# KMO_IO_MV8.net
KiCad netlist of a schematic drawn in EAGLE
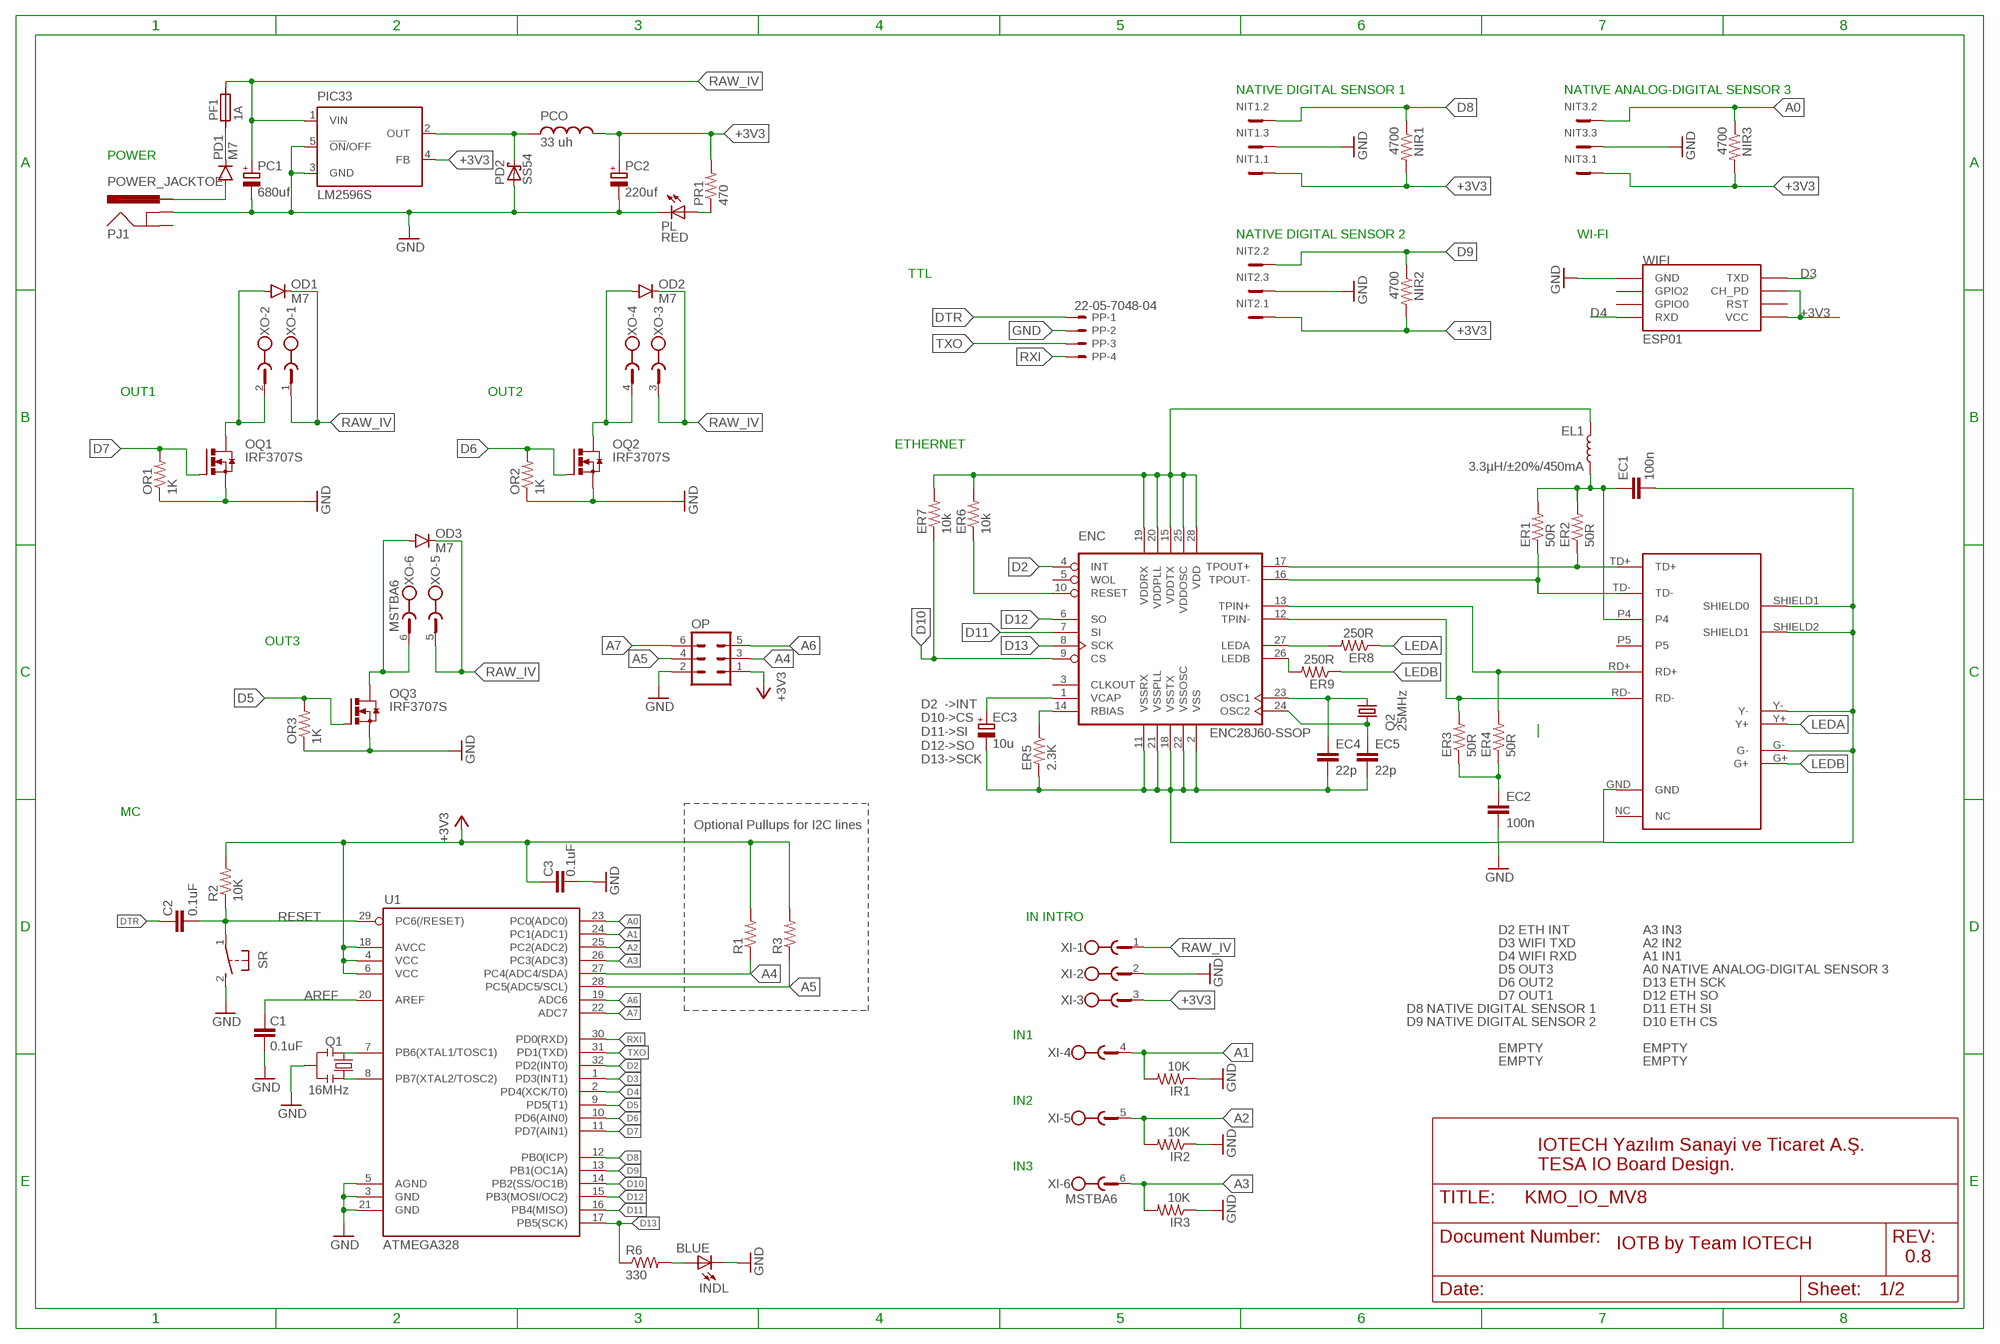
[diagram p0: schematic, sheet 1]
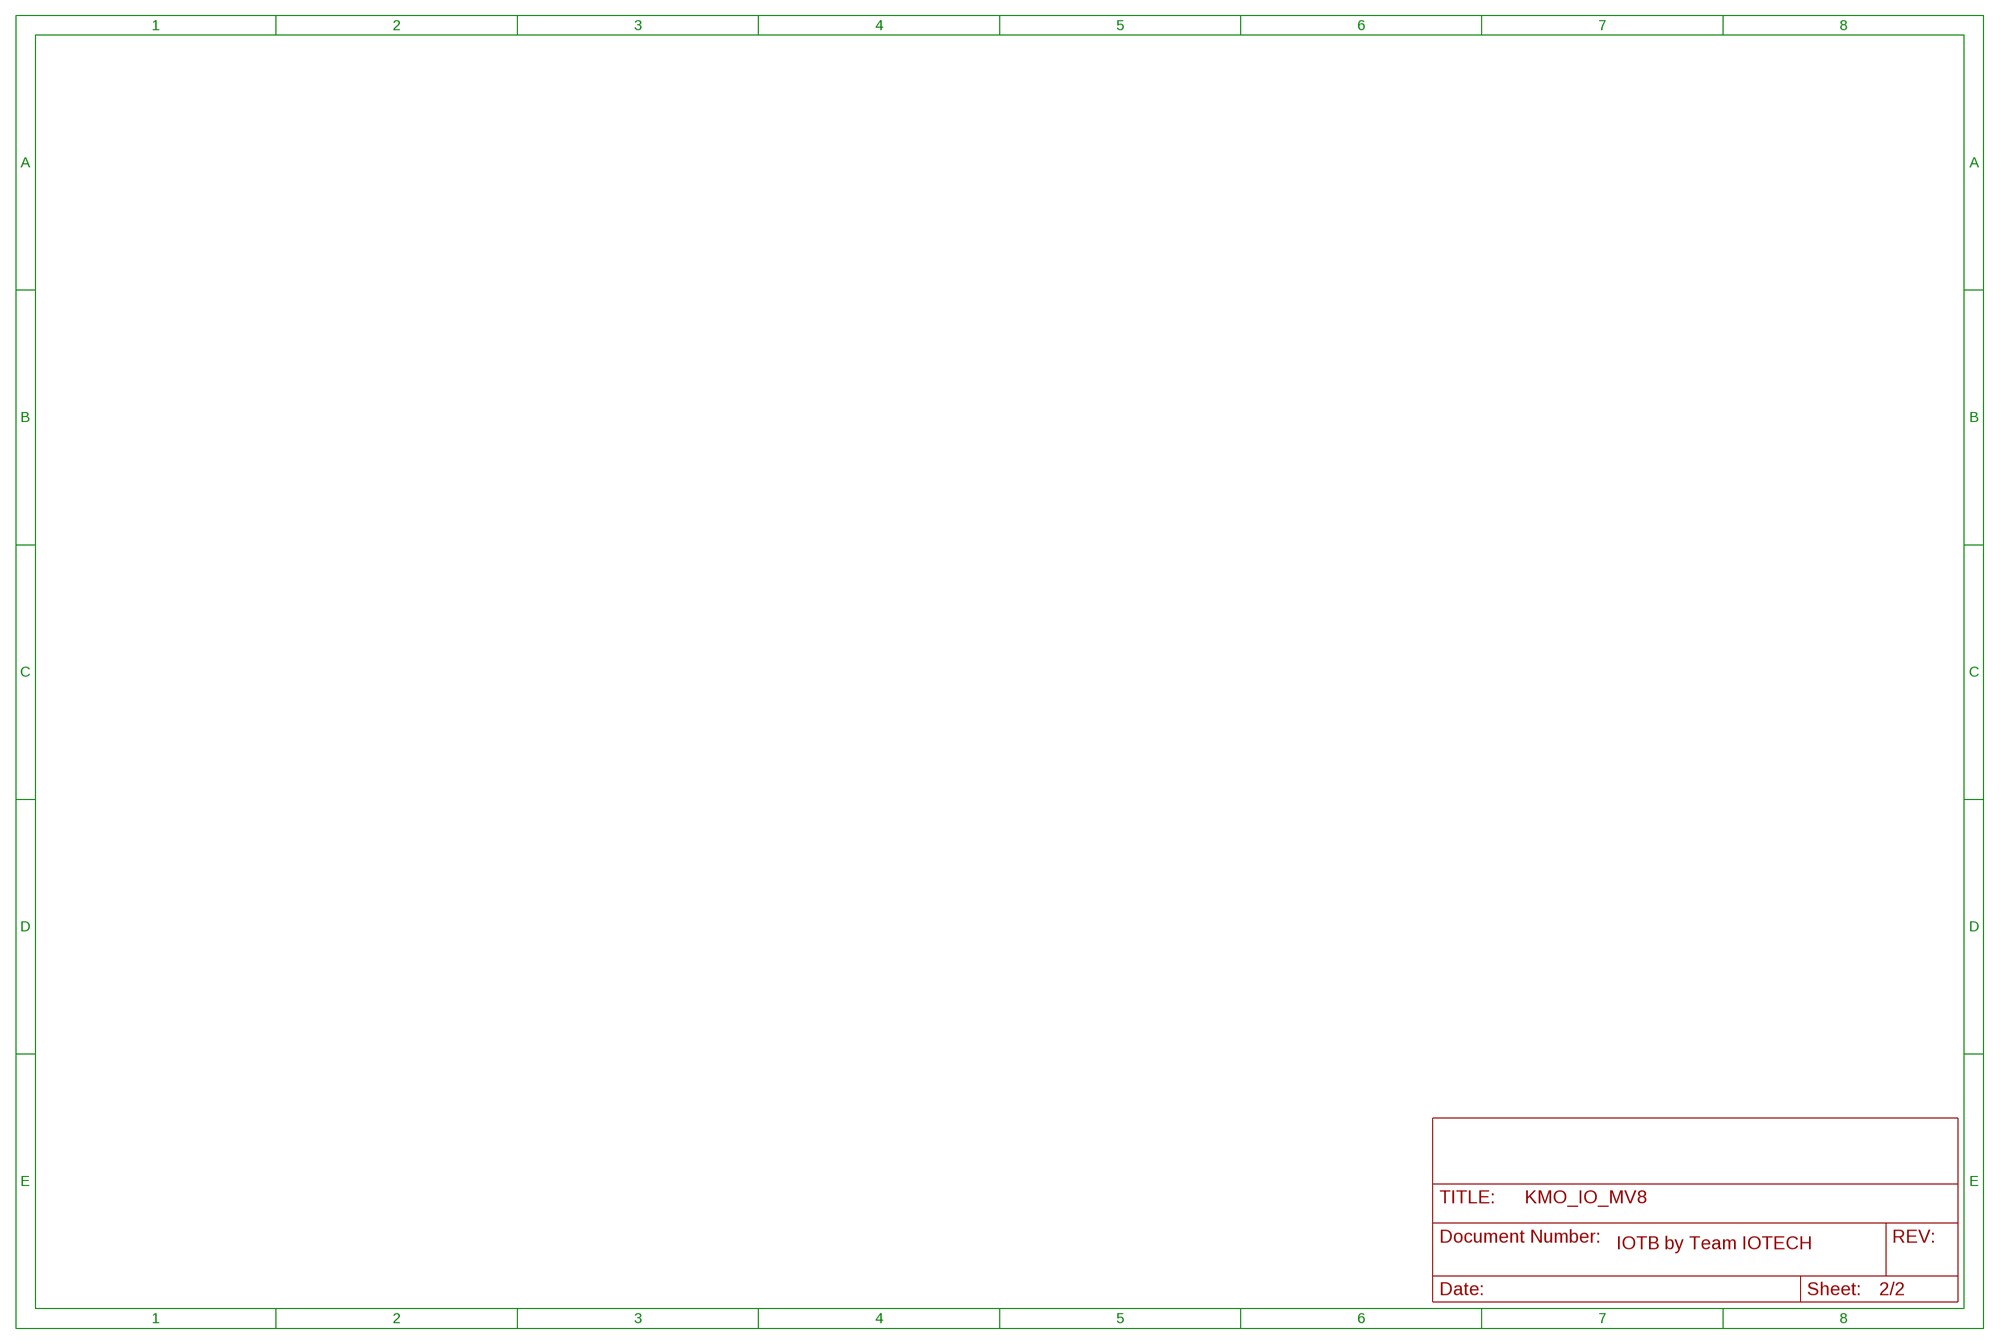
[diagram p1: schematic, sheet 2]

(export (version "E")
  (design (tool "Eeschema 10.0.6"))
  (components
    (comp (ref "C1")
      (value "0.1uF")
      (footprint "eagle-import:0805")
      (libsource (lib "eagle-import") (part "CAP0805"))
    )
    (comp (ref "C2")
      (value "0.1uF")
      (footprint "eagle-import:0805")
      (libsource (lib "eagle-import") (part "CAP0805"))
    )
    (comp (ref "C3")
      (value "0.1uF")
      (footprint "eagle-import:0805")
      (libsource (lib "eagle-import") (part "CAP0805"))
    )
    (comp (ref "EC1")
      (value "100n")
      (footprint "eagle-import:0805")
      (libsource (lib "eagle-import") (part "CAP0805"))
    )
    (comp (ref "EC2")
      (value "100n")
      (footprint "eagle-import:0805")
      (libsource (lib "eagle-import") (part "CAP0805"))
    )
    (comp (ref "EC3")
      (value "10u")
      (footprint "eagle-import:CT3216")
      (libsource (lib "eagle-import") (part "CPOL-EUCT3216"))
    )
    (comp (ref "EC4")
      (value "22p")
      (footprint "eagle-import:0805")
      (libsource (lib "eagle-import") (part "CAP0805"))
    )
    (comp (ref "EC5")
      (value "22p")
      (footprint "eagle-import:0805")
      (libsource (lib "eagle-import") (part "CAP0805"))
    )
    (comp (ref "EL1")
      (value "3.3µH/±20%/450mA")
      (footprint "eagle-import:0805")
      (libsource (lib "eagle-import") (part "INDUCTOR-0805-3.3UH"))
    )
    (comp (ref "ENC")
      (value "ENC28J60-SSOP")
      (footprint "eagle-import:SSOP28")
      (libsource (lib "eagle-import") (part "ENC28J60-SSOP"))
    )
    (comp (ref "ER1")
      (value "50R")
      (footprint "eagle-import:0805")
      (libsource (lib "eagle-import") (part "RESISTOR0805-RES"))
    )
    (comp (ref "ER2")
      (value "50R")
      (footprint "eagle-import:0805")
      (libsource (lib "eagle-import") (part "RESISTOR0805-RES"))
    )
    (comp (ref "ER3")
      (value "50R")
      (footprint "eagle-import:0805")
      (libsource (lib "eagle-import") (part "RESISTOR0805-RES"))
    )
    (comp (ref "ER4")
      (value "50R")
      (footprint "eagle-import:0805")
      (libsource (lib "eagle-import") (part "RESISTOR0805-RES"))
    )
    (comp (ref "ER5")
      (value "2.3K")
      (footprint "eagle-import:0805")
      (libsource (lib "eagle-import") (part "RESISTOR0805-RES"))
    )
    (comp (ref "ER6")
      (value "10k")
      (footprint "eagle-import:0805")
      (libsource (lib "eagle-import") (part "RESISTOR0805-RES"))
    )
    (comp (ref "ER7")
      (value "10k")
      (footprint "eagle-import:0805")
      (libsource (lib "eagle-import") (part "RESISTOR0805-RES"))
    )
    (comp (ref "ER8")
      (value "250R")
      (footprint "eagle-import:0805")
      (libsource (lib "eagle-import") (part "RESISTOR0805-RES"))
    )
    (comp (ref "ER9")
      (value "250R")
      (footprint "eagle-import:0805")
      (libsource (lib "eagle-import") (part "RESISTOR0805-RES"))
    )
    (comp (ref "INDL")
      (value "BLUE")
      (footprint "eagle-import:CHIP-LED0805")
      (libsource (lib "eagle-import") (part "LEDCHIP-LED0805"))
    )
    (comp (ref "IR1")
      (value "10K")
      (footprint "eagle-import:0805")
      (libsource (lib "eagle-import") (part "RESISTOR0805-RES"))
    )
    (comp (ref "IR2")
      (value "10K")
      (footprint "eagle-import:0805")
      (libsource (lib "eagle-import") (part "RESISTOR0805-RES"))
    )
    (comp (ref "IR3")
      (value "10K")
      (footprint "eagle-import:0805")
      (libsource (lib "eagle-import") (part "RESISTOR0805-RES"))
    )
    (comp (ref "NIR1")
      (value "4700")
      (footprint "eagle-import:0805")
      (libsource (lib "eagle-import") (part "RESISTOR0805-RES"))
    )
    (comp (ref "NIR2")
      (value "4700")
      (footprint "eagle-import:0805")
      (libsource (lib "eagle-import") (part "RESISTOR0805-RES"))
    )
    (comp (ref "NIR3")
      (value "4700")
      (footprint "eagle-import:0805")
      (libsource (lib "eagle-import") (part "RESISTOR0805-RES"))
    )
    (comp (ref "NIT1")
      (value "MC3")
      (footprint "eagle-import:MC3")
      (libsource (lib "eagle-import") (part "MC3"))
    )
    (comp (ref "NIT2")
      (value "MC3")
      (footprint "eagle-import:MC3")
      (libsource (lib "eagle-import") (part "MC3"))
    )
    (comp (ref "NIT3")
      (value "MC3")
      (footprint "eagle-import:MC3")
      (libsource (lib "eagle-import") (part "MC3"))
    )
    (comp (ref "OD1")
      (value "M7")
      (footprint "eagle-import:SMA-DIODE")
      (libsource (lib "eagle-import") (part "DIODESMA"))
    )
    (comp (ref "OD2")
      (value "M7")
      (footprint "eagle-import:SMA-DIODE")
      (libsource (lib "eagle-import") (part "DIODESMA"))
    )
    (comp (ref "OD3")
      (value "M7")
      (footprint "eagle-import:SMA-DIODE")
      (libsource (lib "eagle-import") (part "DIODESMA"))
    )
    (comp (ref "OP")
      (value "MA03-2")
      (footprint "eagle-import:MA03-2")
      (libsource (lib "eagle-import") (part "MA03-2"))
    )
    (comp (ref "OQ1")
      (value "IRF3707S")
      (footprint "eagle-import:D2PACK")
      (libsource (lib "eagle-import") (part "IRF3704S"))
    )
    (comp (ref "OQ2")
      (value "IRF3707S")
      (footprint "eagle-import:D2PACK")
      (libsource (lib "eagle-import") (part "IRF3704S"))
    )
    (comp (ref "OQ3")
      (value "IRF3707S")
      (footprint "eagle-import:D2PACK")
      (libsource (lib "eagle-import") (part "IRF3704S"))
    )
    (comp (ref "OR1")
      (value "1K")
      (footprint "eagle-import:0805")
      (libsource (lib "eagle-import") (part "RESISTOR0805-RES"))
    )
    (comp (ref "OR2")
      (value "1K")
      (footprint "eagle-import:0805")
      (libsource (lib "eagle-import") (part "RESISTOR0805-RES"))
    )
    (comp (ref "OR3")
      (value "1K")
      (footprint "eagle-import:0805")
      (libsource (lib "eagle-import") (part "RESISTOR0805-RES"))
    )
    (comp (ref "PC1")
      (value "680uf")
      (footprint "eagle-import:140CLH-1010")
      (libsource (lib "eagle-import") (part "CPOL-EU140CLH-1010"))
    )
    (comp (ref "PC2")
      (value "220uf")
      (footprint "eagle-import:140CLH-1010")
      (libsource (lib "eagle-import") (part "CPOL-EU140CLH-1010"))
    )
    (comp (ref "PCO")
      (value "33 uh")
      (footprint "eagle-import:MSS1260")
      (libsource (lib "eagle-import") (part "MSS1260"))
    )
    (comp (ref "PD1")
      (value "M7")
      (footprint "eagle-import:SMA-DIODE")
      (libsource (lib "eagle-import") (part "DIODESMA"))
    )
    (comp (ref "PD2")
      (value "SS54")
      (footprint "eagle-import:SMB")
      (libsource (lib "eagle-import") (part "SCHOTTKY-DIODESMD"))
    )
    (comp (ref "PF1")
      (value "1A")
      (footprint "eagle-import:1820")
      (libsource (lib "eagle-import") (part "SIBA194600"))
    )
    (comp (ref "PIC33")
      (value "LM2596S")
      (footprint "eagle-import:TO263-5")
      (fields (field (name "MF") "NATIONAL SEMICONDUCTOR") (field (name "MPN") "LM2596S-ADJ/NOPB"))
      (libsource (lib "eagle-import") (part "LM2596S"))
    )
    (comp (ref "PJ1")
      (value "POWER_JACKTOE")
      (footprint "eagle-import:POWER_JACK_SMD_OVERPASTE_TOE")
      (libsource (lib "eagle-import") (part "POWER_JACKTOE"))
    )
    (comp (ref "PL")
      (value "RED")
      (footprint "eagle-import:CHIP-LED0805")
      (libsource (lib "eagle-import") (part "LEDCHIP-LED0805"))
    )
    (comp (ref "PP")
      (value "22-05-7048-04")
      (footprint "eagle-import:7395-04")
      (fields (field (name "MF") "MOLEX"))
      (libsource (lib "eagle-import") (part "22-?-0405-7048"))
    )
    (comp (ref "PR1")
      (value "470")
      (footprint "eagle-import:0805")
      (libsource (lib "eagle-import") (part "RESISTOR0805-RES"))
    )
    (comp (ref "Q1")
      (value "16MHz")
      (footprint "eagle-import:RESONATOR-SMD-1_1")
      (libsource (lib "eagle-import") (part "RESONATOR1{colon}1"))
    )
    (comp (ref "Q2")
      (value "25MHz")
      (footprint "eagle-import:5.0X3.2_2")
      (libsource (lib "eagle-import") (part "KX-9B"))
    )
    (comp (ref "R1")
      (value "RESISTOR0805-RES")
      (footprint "eagle-import:0805")
      (libsource (lib "eagle-import") (part "RESISTOR0805-RES"))
    )
    (comp (ref "R2")
      (value "10K")
      (footprint "eagle-import:0805")
      (libsource (lib "eagle-import") (part "RESISTOR0805-RES"))
    )
    (comp (ref "R3")
      (value "RESISTOR0805-RES")
      (footprint "eagle-import:0805")
      (libsource (lib "eagle-import") (part "RESISTOR0805-RES"))
    )
    (comp (ref "R6")
      (value "330")
      (footprint "eagle-import:0805")
      (libsource (lib "eagle-import") (part "RESISTOR0805-RES"))
    )
    (comp (ref "SR")
      (value "31-XX")
      (footprint "eagle-import:B3F-31XX")
      (fields (field (name "MPN") "B3F-3100"))
      (libsource (lib "eagle-import") (part "31-XX"))
    )
    (comp (ref "U$2")
      (value "HR911105A")
      (footprint "eagle-import:RJ45")
      (libsource (lib "eagle-import") (part "HR911105A"))
    )
    (comp (ref "U1")
      (value "ATMEGA328")
      (footprint "eagle-import:TQFP32-08")
      (libsource (lib "eagle-import") (part "ATMEGA168"))
    )
    (comp (ref "WIFI")
      (value "ESP01")
      (footprint "eagle-import:ESP01")
      (libsource (lib "eagle-import") (part "ESP01"))
    )
    (comp (ref "XI")
      (value "MSTBA6")
      (footprint "eagle-import:MSTBA6")
      (fields (field (name "MF") "FARNELL") (field (name "MPN") "1757284"))
      (libsource (lib "eagle-import") (part "MSTBA6"))
    )
    (comp (ref "XO")
      (value "MSTBA6")
      (footprint "eagle-import:MSTBA6")
      (fields (field (name "MF") "FARNELL") (field (name "MPN") "1757284"))
      (libsource (lib "eagle-import") (part "MSTBA6"))
    )
  )
  (nets
    (net (code "1") (name "+3V3") (class "Default")
      (node (ref "C3") (pin "2") (pinfunction "2_2") (pintype "passive"))
      (node (ref "EL1") (pin "1") (pinfunction "1_1") (pintype "passive"))
      (node (ref "ENC") (pin "15") (pinfunction "VDDTX_15") (pintype "power_in"))
      (node (ref "ENC") (pin "19") (pinfunction "VDDRX_19") (pintype "power_in"))
      (node (ref "ENC") (pin "20") (pinfunction "VDDPLL_20") (pintype "power_in"))
      (node (ref "ENC") (pin "25") (pinfunction "VDDOSC_25") (pintype "power_in"))
      (node (ref "ENC") (pin "28") (pinfunction "VDD_28") (pintype "power_in"))
      (node (ref "ER6") (pin "2") (pinfunction "2_2") (pintype "passive"))
      (node (ref "ER7") (pin "2") (pinfunction "2_2") (pintype "passive"))
      (node (ref "NIR1") (pin "2") (pinfunction "2_2") (pintype "passive"))
      (node (ref "NIR2") (pin "2") (pinfunction "2_2") (pintype "passive"))
      (node (ref "NIR3") (pin "2") (pinfunction "2_2") (pintype "passive"))
      (node (ref "NIT1") (pin "1") (pinfunction "SK_1") (pintype "passive"))
      (node (ref "NIT2") (pin "1") (pinfunction "SK_1") (pintype "passive"))
      (node (ref "NIT3") (pin "1") (pinfunction "SK_1") (pintype "passive"))
      (node (ref "OP") (pin "1") (pinfunction "1_1") (pintype "passive"))
      (node (ref "PC2") (pin "+") (pinfunction "+_+") (pintype "passive"))
      (node (ref "PCO") (pin "P$1") (pinfunction "P$1_P$1") (pintype "passive"))
      (node (ref "PIC33") (pin "4") (pinfunction "FB_4") (pintype "input"))
      (node (ref "PR1") (pin "2") (pinfunction "2_2") (pintype "passive"))
      (node (ref "R1") (pin "2") (pinfunction "2_2") (pintype "passive"))
      (node (ref "R2") (pin "2") (pinfunction "2_2") (pintype "passive"))
      (node (ref "R3") (pin "2") (pinfunction "2_2") (pintype "passive"))
      (node (ref "U1") (pin "18") (pinfunction "AVCC_18") (pintype "bidirectional"))
      (node (ref "U1") (pin "4") (pinfunction "VCC_4") (pintype "bidirectional"))
      (node (ref "U1") (pin "6") (pinfunction "VCC_6") (pintype "bidirectional"))
      (node (ref "WIFI") (pin "CH_PD") (pinfunction "CH_PD_CH_PD") (pintype "bidirectional"))
      (node (ref "WIFI") (pin "VCC") (pinfunction "VCC_VCC") (pintype "bidirectional"))
      (node (ref "XI") (pin "3") (pinfunction "1_3") (pintype "passive"))
    )
    (net (code "2") (name "A0") (class "Default")
      (node (ref "NIR3") (pin "1") (pinfunction "1_1") (pintype "passive"))
      (node (ref "NIT3") (pin "2") (pinfunction "SK_2") (pintype "passive"))
      (node (ref "U1") (pin "23") (pinfunction "PC0(ADC0)_23") (pintype "bidirectional"))
    )
    (net (code "3") (name "A1") (class "Default")
      (node (ref "IR1") (pin "2") (pinfunction "2_2") (pintype "passive"))
      (node (ref "U1") (pin "24") (pinfunction "PC1(ADC1)_24") (pintype "bidirectional"))
      (node (ref "XI") (pin "4") (pinfunction "1_4") (pintype "passive"))
    )
    (net (code "4") (name "A2") (class "Default")
      (node (ref "IR2") (pin "2") (pinfunction "2_2") (pintype "passive"))
      (node (ref "U1") (pin "25") (pinfunction "PC2(ADC2)_25") (pintype "bidirectional"))
      (node (ref "XI") (pin "5") (pinfunction "1_5") (pintype "passive"))
    )
    (net (code "5") (name "A3") (class "Default")
      (node (ref "IR3") (pin "2") (pinfunction "2_2") (pintype "passive"))
      (node (ref "U1") (pin "26") (pinfunction "PC3(ADC3)_26") (pintype "bidirectional"))
      (node (ref "XI") (pin "6") (pinfunction "1_6") (pintype "passive"))
    )
    (net (code "6") (name "A4") (class "Default")
      (node (ref "OP") (pin "3") (pinfunction "3_3") (pintype "passive"))
      (node (ref "R1") (pin "1") (pinfunction "1_1") (pintype "passive"))
      (node (ref "U1") (pin "27") (pinfunction "PC4(ADC4/SDA)_27") (pintype "bidirectional"))
    )
    (net (code "7") (name "A5") (class "Default")
      (node (ref "OP") (pin "4") (pinfunction "4_4") (pintype "passive"))
      (node (ref "R3") (pin "1") (pinfunction "1_1") (pintype "passive"))
      (node (ref "U1") (pin "28") (pinfunction "PC5(ADC5/SCL)_28") (pintype "bidirectional"))
    )
    (net (code "8") (name "A6") (class "Default")
      (node (ref "OP") (pin "5") (pinfunction "5_5") (pintype "passive"))
      (node (ref "U1") (pin "19") (pinfunction "ADC6_19") (pintype "bidirectional"))
    )
    (net (code "9") (name "A7") (class "Default")
      (node (ref "OP") (pin "6") (pinfunction "6_6") (pintype "passive"))
      (node (ref "U1") (pin "22") (pinfunction "ADC7_22") (pintype "bidirectional"))
    )
    (net (code "10") (name "AREF") (class "Default")
      (node (ref "C1") (pin "2") (pinfunction "2_2") (pintype "passive"))
      (node (ref "U1") (pin "20") (pinfunction "AREF_20") (pintype "bidirectional"))
    )
    (net (code "11") (name "D2") (class "Default")
      (node (ref "ENC") (pin "4") (pinfunction "INT_4") (pintype "output"))
      (node (ref "U1") (pin "32") (pinfunction "PD2(INT0)_32") (pintype "bidirectional"))
    )
    (net (code "12") (name "D3") (class "Default")
      (node (ref "U1") (pin "1") (pinfunction "PD3(INT1)_1") (pintype "bidirectional"))
      (node (ref "WIFI") (pin "TX") (pinfunction "TXD_TX") (pintype "bidirectional"))
    )
    (net (code "13") (name "D4") (class "Default")
      (node (ref "U1") (pin "2") (pinfunction "PD4(XCK/T0)_2") (pintype "bidirectional"))
      (node (ref "WIFI") (pin "RX") (pinfunction "RXD_RX") (pintype "bidirectional"))
    )
    (net (code "14") (name "D5") (class "Default")
      (node (ref "OQ3") (pin "1") (pinfunction "G_1") (pintype "passive"))
      (node (ref "OR3") (pin "2") (pinfunction "2_2") (pintype "passive"))
      (node (ref "U1") (pin "9") (pinfunction "PD5(T1)_9") (pintype "bidirectional"))
    )
    (net (code "15") (name "D6") (class "Default")
      (node (ref "OQ2") (pin "1") (pinfunction "G_1") (pintype "passive"))
      (node (ref "OR2") (pin "2") (pinfunction "2_2") (pintype "passive"))
      (node (ref "U1") (pin "10") (pinfunction "PD6(AIN0)_10") (pintype "bidirectional"))
    )
    (net (code "16") (name "D7") (class "Default")
      (node (ref "OQ1") (pin "1") (pinfunction "G_1") (pintype "passive"))
      (node (ref "OR1") (pin "2") (pinfunction "2_2") (pintype "passive"))
      (node (ref "U1") (pin "11") (pinfunction "PD7(AIN1)_11") (pintype "bidirectional"))
    )
    (net (code "17") (name "D8") (class "Default")
      (node (ref "NIR1") (pin "1") (pinfunction "1_1") (pintype "passive"))
      (node (ref "NIT1") (pin "2") (pinfunction "SK_2") (pintype "passive"))
      (node (ref "U1") (pin "12") (pinfunction "PB0(ICP)_12") (pintype "bidirectional"))
    )
    (net (code "18") (name "D9") (class "Default")
      (node (ref "NIR2") (pin "1") (pinfunction "1_1") (pintype "passive"))
      (node (ref "NIT2") (pin "2") (pinfunction "SK_2") (pintype "passive"))
      (node (ref "U1") (pin "13") (pinfunction "PB1(OC1A)_13") (pintype "bidirectional"))
    )
    (net (code "19") (name "D10") (class "Default")
      (node (ref "ENC") (pin "9") (pinfunction "CS_9") (pintype "input"))
      (node (ref "ER7") (pin "1") (pinfunction "1_1") (pintype "passive"))
      (node (ref "U1") (pin "14") (pinfunction "PB2(SS/OC1B)_14") (pintype "bidirectional"))
    )
    (net (code "20") (name "D11") (class "Default")
      (node (ref "ENC") (pin "7") (pinfunction "SI_7") (pintype "input"))
      (node (ref "U1") (pin "16") (pinfunction "PB4(MISO)_16") (pintype "bidirectional"))
    )
    (net (code "21") (name "D12") (class "Default")
      (node (ref "ENC") (pin "6") (pinfunction "SO_6") (pintype "output"))
      (node (ref "U1") (pin "15") (pinfunction "PB3(MOSI/OC2)_15") (pintype "bidirectional"))
    )
    (net (code "22") (name "D13") (class "Default")
      (node (ref "ENC") (pin "8") (pinfunction "SCK_8") (pintype "input"))
      (node (ref "R6") (pin "1") (pinfunction "1_1") (pintype "passive"))
      (node (ref "U1") (pin "17") (pinfunction "PB5(SCK)_17") (pintype "bidirectional"))
    )
    (net (code "23") (name "DTR") (class "Default")
      (node (ref "C2") (pin "2") (pinfunction "2_2") (pintype "passive"))
      (node (ref "PP") (pin "1") (pinfunction "S_1") (pintype "passive"))
    )
    (net (code "24") (name "GND") (class "Default")
      (node (ref "C1") (pin "1") (pinfunction "1_1") (pintype "passive"))
      (node (ref "C3") (pin "1") (pinfunction "1_1") (pintype "passive"))
      (node (ref "EC1") (pin "2") (pinfunction "2_2") (pintype "passive"))
      (node (ref "EC2") (pin "2") (pinfunction "2_2") (pintype "passive"))
      (node (ref "EC3") (pin "-") (pinfunction "-_-") (pintype "passive"))
      (node (ref "EC4") (pin "2") (pinfunction "2_2") (pintype "passive"))
      (node (ref "EC5") (pin "2") (pinfunction "2_2") (pintype "passive"))
      (node (ref "ENC") (pin "11") (pinfunction "VSSRX_11") (pintype "power_in"))
      (node (ref "ENC") (pin "18") (pinfunction "VSSTX_18") (pintype "power_in"))
      (node (ref "ENC") (pin "2") (pinfunction "VSS_2") (pintype "power_in"))
      (node (ref "ENC") (pin "21") (pinfunction "VSSPLL_21") (pintype "power_in"))
      (node (ref "ENC") (pin "22") (pinfunction "VSSOSC_22") (pintype "power_in"))
      (node (ref "ER5") (pin "2") (pinfunction "2_2") (pintype "passive"))
      (node (ref "INDL") (pin "C") (pinfunction "C_C") (pintype "passive"))
      (node (ref "IR1") (pin "1") (pinfunction "1_1") (pintype "passive"))
      (node (ref "IR2") (pin "1") (pinfunction "1_1") (pintype "passive"))
      (node (ref "IR3") (pin "1") (pinfunction "1_1") (pintype "passive"))
      (node (ref "NIT1") (pin "3") (pinfunction "SK_3") (pintype "passive"))
      (node (ref "NIT2") (pin "3") (pinfunction "SK_3") (pintype "passive"))
      (node (ref "NIT3") (pin "3") (pinfunction "SK_3") (pintype "passive"))
      (node (ref "OP") (pin "2") (pinfunction "2_2") (pintype "passive"))
      (node (ref "OQ1") (pin "3") (pinfunction "S_3") (pintype "passive"))
      (node (ref "OQ2") (pin "3") (pinfunction "S_3") (pintype "passive"))
      (node (ref "OQ3") (pin "3") (pinfunction "S_3") (pintype "passive"))
      (node (ref "OR1") (pin "1") (pinfunction "1_1") (pintype "passive"))
      (node (ref "OR2") (pin "1") (pinfunction "1_1") (pintype "passive"))
      (node (ref "OR3") (pin "1") (pinfunction "1_1") (pintype "passive"))
      (node (ref "PC1") (pin "-") (pinfunction "-_-") (pintype "passive"))
      (node (ref "PC2") (pin "-") (pinfunction "-_-") (pintype "passive"))
      (node (ref "PD2") (pin "A") (pinfunction "A_A") (pintype "passive"))
      (node (ref "PIC33") (pin "3") (pinfunction "GND_3") (pintype "power_in"))
      (node (ref "PIC33") (pin "5") (pinfunction "~{ON}/OFF_5") (pintype "input"))
      (node (ref "PJ1") (pin "GND") (pinfunction "GNDBREAK_GND") (pintype "bidirectional"))
      (node (ref "PL") (pin "C") (pinfunction "C_C") (pintype "passive"))
      (node (ref "PP") (pin "2") (pinfunction "S_2") (pintype "passive"))
      (node (ref "Q1") (pin "2") (pinfunction "2_2") (pintype "passive"))
      (node (ref "SR") (pin "2") (pinfunction "S_2") (pintype "passive"))
      (node (ref "U$2") (pin "G-") (pinfunction "G-_G-") (pintype "bidirectional"))
      (node (ref "U$2") (pin "GND") (pinfunction "GND_GND") (pintype "bidirectional"))
      (node (ref "U$2") (pin "SHIELD1") (pinfunction "SHIELD0_SHIELD1") (pintype "bidirectional"))
      (node (ref "U$2") (pin "SHIELD2") (pinfunction "SHIELD1_SHIELD2") (pintype "bidirectional"))
      (node (ref "U$2") (pin "Y-") (pinfunction "Y-_Y-") (pintype "bidirectional"))
      (node (ref "U1") (pin "21") (pinfunction "GND_21") (pintype "bidirectional"))
      (node (ref "U1") (pin "3") (pinfunction "GND_3") (pintype "bidirectional"))
      (node (ref "U1") (pin "5") (pinfunction "AGND_5") (pintype "bidirectional"))
      (node (ref "WIFI") (pin "GND") (pinfunction "GND_GND") (pintype "bidirectional"))
      (node (ref "XI") (pin "2") (pinfunction "1_2") (pintype "passive"))
    )
    (net (code "25") (name "LEDA") (class "Default")
      (node (ref "ER8") (pin "1") (pinfunction "1_1") (pintype "passive"))
      (node (ref "U$2") (pin "Y+") (pinfunction "Y+_Y+") (pintype "bidirectional"))
    )
    (net (code "26") (name "LEDB") (class "Default")
      (node (ref "ER9") (pin "1") (pinfunction "1_1") (pintype "passive"))
      (node (ref "U$2") (pin "G+") (pinfunction "G+_G+") (pintype "bidirectional"))
    )
    (net (code "27") (name "Net-(EC1-Pad1)") (class "Default")
      (node (ref "EC1") (pin "1") (pinfunction "1_1") (pintype "passive"))
      (node (ref "EL1") (pin "2") (pinfunction "2_2") (pintype "passive"))
      (node (ref "ER1") (pin "2") (pinfunction "2_2") (pintype "passive"))
      (node (ref "ER2") (pin "2") (pinfunction "2_2") (pintype "passive"))
      (node (ref "U$2") (pin "P4") (pinfunction "P4_P4") (pintype "bidirectional"))
    )
    (net (code "28") (name "Net-(EC2-Pad1)") (class "Default")
      (node (ref "EC2") (pin "1") (pinfunction "1_1") (pintype "passive"))
      (node (ref "ER3") (pin "1") (pinfunction "1_1") (pintype "passive"))
      (node (ref "ER4") (pin "1") (pinfunction "1_1") (pintype "passive"))
    )
    (net (code "29") (name "Net-(ENC-LEDA)") (class "Default")
      (node (ref "ENC") (pin "27") (pinfunction "LEDA_27") (pintype "output"))
      (node (ref "ER8") (pin "2") (pinfunction "2_2") (pintype "passive"))
    )
    (net (code "30") (name "Net-(ENC-LEDB)") (class "Default")
      (node (ref "ENC") (pin "26") (pinfunction "LEDB_26") (pintype "output"))
      (node (ref "ER9") (pin "2") (pinfunction "2_2") (pintype "passive"))
    )
    (net (code "31") (name "Net-(ENC-OSC1)") (class "Default")
      (node (ref "EC4") (pin "1") (pinfunction "1_1") (pintype "passive"))
      (node (ref "ENC") (pin "23") (pinfunction "OSC1_23") (pintype "input"))
      (node (ref "Q2") (pin "2") (pinfunction "2_2") (pintype "passive"))
    )
    (net (code "32") (name "Net-(ENC-OSC2)") (class "Default")
      (node (ref "EC5") (pin "1") (pinfunction "1_1") (pintype "passive"))
      (node (ref "ENC") (pin "24") (pinfunction "OSC2_24") (pintype "output"))
      (node (ref "Q2") (pin "1") (pinfunction "1_1") (pintype "passive"))
    )
    (net (code "33") (name "Net-(ENC-RBIAS)") (class "Default")
      (node (ref "ENC") (pin "14") (pinfunction "RBIAS_14") (pintype "passive"))
      (node (ref "ER5") (pin "1") (pinfunction "1_1") (pintype "passive"))
    )
    (net (code "34") (name "Net-(ENC-RESET)") (class "Default")
      (node (ref "ENC") (pin "10") (pinfunction "RESET_10") (pintype "input"))
      (node (ref "ER6") (pin "1") (pinfunction "1_1") (pintype "passive"))
    )
    (net (code "35") (name "Net-(ENC-TPIN+)") (class "Default")
      (node (ref "ENC") (pin "13") (pinfunction "TPIN+_13") (pintype "input"))
      (node (ref "ER4") (pin "2") (pinfunction "2_2") (pintype "passive"))
      (node (ref "U$2") (pin "RD+") (pinfunction "RD+_RD+") (pintype "bidirectional"))
    )
    (net (code "36") (name "Net-(ENC-TPIN-)") (class "Default")
      (node (ref "ENC") (pin "12") (pinfunction "TPIN-_12") (pintype "input"))
      (node (ref "ER3") (pin "2") (pinfunction "2_2") (pintype "passive"))
      (node (ref "U$2") (pin "RD-") (pinfunction "RD-_RD-") (pintype "bidirectional"))
    )
    (net (code "37") (name "Net-(ENC-TPOUT+)") (class "Default")
      (node (ref "ENC") (pin "17") (pinfunction "TPOUT+_17") (pintype "output"))
      (node (ref "ER2") (pin "1") (pinfunction "1_1") (pintype "passive"))
      (node (ref "U$2") (pin "TD+") (pinfunction "TD+_TD+") (pintype "bidirectional"))
    )
    (net (code "38") (name "Net-(ENC-TPOUT-)") (class "Default")
      (node (ref "ENC") (pin "16") (pinfunction "TPOUT-_16") (pintype "output"))
      (node (ref "ER1") (pin "1") (pinfunction "1_1") (pintype "passive"))
      (node (ref "U$2") (pin "TD-") (pinfunction "TD-_TD-") (pintype "bidirectional"))
    )
    (net (code "39") (name "Net-(ENC-VCAP)") (class "Default")
      (node (ref "EC3") (pin "+") (pinfunction "+_+") (pintype "passive"))
      (node (ref "ENC") (pin "1") (pinfunction "VCAP_1") (pintype "power_in"))
    )
    (net (code "40") (name "Net-(INDL-PadA)") (class "Default")
      (node (ref "INDL") (pin "A") (pinfunction "A_A") (pintype "passive"))
      (node (ref "R6") (pin "2") (pinfunction "2_2") (pintype "passive"))
    )
    (net (code "41") (name "Net-(OQ1-D)") (class "Default")
      (node (ref "OD1") (pin "A") (pinfunction "A_A") (pintype "passive"))
      (node (ref "OQ1") (pin "2") (pinfunction "D_2") (pintype "passive"))
      (node (ref "XO") (pin "2") (pinfunction "1_2") (pintype "passive"))
    )
    (net (code "42") (name "Net-(OQ2-D)") (class "Default")
      (node (ref "OD2") (pin "A") (pinfunction "A_A") (pintype "passive"))
      (node (ref "OQ2") (pin "2") (pinfunction "D_2") (pintype "passive"))
      (node (ref "XO") (pin "4") (pinfunction "1_4") (pintype "passive"))
    )
    (net (code "43") (name "Net-(OQ3-D)") (class "Default")
      (node (ref "OD3") (pin "A") (pinfunction "A_A") (pintype "passive"))
      (node (ref "OQ3") (pin "2") (pinfunction "D_2") (pintype "passive"))
      (node (ref "XO") (pin "6") (pinfunction "1_6") (pintype "passive"))
    )
    (net (code "44") (name "Net-(PD1-PadC)") (class "Default")
      (node (ref "PD1") (pin "C") (pinfunction "C_C") (pintype "passive"))
      (node (ref "PF1") (pin "1") (pinfunction "1_1") (pintype "passive"))
    )
    (net (code "45") (name "Net-(PIC33-OUT)") (class "Default")
      (node (ref "PCO") (pin "P$2") (pinfunction "P$2_P$2") (pintype "passive"))
      (node (ref "PD2") (pin "C") (pinfunction "C_C") (pintype "passive"))
      (node (ref "PIC33") (pin "2") (pinfunction "OUT_2") (pintype "output"))
    )
    (net (code "46") (name "Net-(PJ1-PWR)") (class "Default")
      (node (ref "PD1") (pin "A") (pinfunction "A_A") (pintype "passive"))
      (node (ref "PJ1") (pin "VIN0") (pinfunction "PWR_VIN0") (pintype "bidirectional"))
    )
    (net (code "47") (name "Net-(PL-PadA)") (class "Default")
      (node (ref "PL") (pin "A") (pinfunction "A_A") (pintype "passive"))
      (node (ref "PR1") (pin "1") (pinfunction "1_1") (pintype "passive"))
    )
    (net (code "48") (name "Net-(U1-PB6(XTAL1{slash}TOSC1))") (class "Default")
      (node (ref "Q1") (pin "1") (pinfunction "1_1") (pintype "passive"))
      (node (ref "U1") (pin "7") (pinfunction "PB6(XTAL1/TOSC1)_7") (pintype "bidirectional"))
    )
    (net (code "49") (name "Net-(U1-PB7(XTAL2{slash}TOSC2))") (class "Default")
      (node (ref "Q1") (pin "3") (pinfunction "3_3") (pintype "passive"))
      (node (ref "U1") (pin "8") (pinfunction "PB7(XTAL2/TOSC2)_8") (pintype "bidirectional"))
    )
    (net (code "50") (name "RAW_IV") (class "Default")
      (node (ref "OD1") (pin "C") (pinfunction "C_C") (pintype "passive"))
      (node (ref "OD2") (pin "C") (pinfunction "C_C") (pintype "passive"))
      (node (ref "OD3") (pin "C") (pinfunction "C_C") (pintype "passive"))
      (node (ref "PC1") (pin "+") (pinfunction "+_+") (pintype "passive"))
      (node (ref "PF1") (pin "2") (pinfunction "2_2") (pintype "passive"))
      (node (ref "PIC33") (pin "1") (pinfunction "VIN_1") (pintype "input"))
      (node (ref "XI") (pin "1") (pinfunction "1_1") (pintype "passive"))
      (node (ref "XO") (pin "1") (pinfunction "1_1") (pintype "passive"))
      (node (ref "XO") (pin "3") (pinfunction "1_3") (pintype "passive"))
      (node (ref "XO") (pin "5") (pinfunction "1_5") (pintype "passive"))
    )
    (net (code "51") (name "RESET") (class "Default")
      (node (ref "C2") (pin "1") (pinfunction "1_1") (pintype "passive"))
      (node (ref "R2") (pin "1") (pinfunction "1_1") (pintype "passive"))
      (node (ref "SR") (pin "1") (pinfunction "P_1") (pintype "passive"))
      (node (ref "U1") (pin "29") (pinfunction "PC6(/RESET)_29") (pintype "bidirectional"))
    )
    (net (code "52") (name "RXI") (class "Default")
      (node (ref "PP") (pin "4") (pinfunction "S_4") (pintype "passive"))
      (node (ref "U1") (pin "30") (pinfunction "PD0(RXD)_30") (pintype "bidirectional"))
    )
    (net (code "53") (name "TXO") (class "Default")
      (node (ref "PP") (pin "3") (pinfunction "S_3") (pintype "passive"))
      (node (ref "U1") (pin "31") (pinfunction "PD1(TXD)_31") (pintype "bidirectional"))
    )
    (net (code "54") (name "unconnected-(ENC-CLKOUT-Pad3)") (class "Default")
      (node (ref "ENC") (pin "3") (pinfunction "CLKOUT_3") (pintype "output"))
    )
    (net (code "55") (name "unconnected-(ENC-WOL-Pad5)") (class "Default")
      (node (ref "ENC") (pin "5") (pinfunction "WOL_5") (pintype "output"))
    )
    (net (code "56") (name "unconnected-(PJ1-GND-PadP$4)") (class "Default")
      (node (ref "PJ1") (pin "P$4") (pinfunction "GND_P$4") (pintype "bidirectional"))
    )
    (net (code "57") (name "unconnected-(U$2-PadNC)") (class "Default")
      (node (ref "U$2") (pin "NC") (pinfunction "NC_NC") (pintype "bidirectional"))
    )
    (net (code "58") (name "unconnected-(U$2-PadP5)") (class "Default")
      (node (ref "U$2") (pin "P5") (pinfunction "P5_P5") (pintype "bidirectional"))
    )
    (net (code "59") (name "unconnected-(WIFI-PadGPIO0)") (class "Default")
      (node (ref "WIFI") (pin "GPIO0") (pinfunction "GPIO0_GPIO0") (pintype "bidirectional"))
    )
    (net (code "60") (name "unconnected-(WIFI-PadGPIO2)") (class "Default")
      (node (ref "WIFI") (pin "GPIO2") (pinfunction "GPIO2_GPIO2") (pintype "bidirectional"))
    )
    (net (code "61") (name "unconnected-(WIFI-PadRST)") (class "Default")
      (node (ref "WIFI") (pin "RST") (pinfunction "RST_RST") (pintype "bidirectional"))
    )
  )
)
